# motorturn.net
KiCad netlist of a schematic drawn in Altium Designer
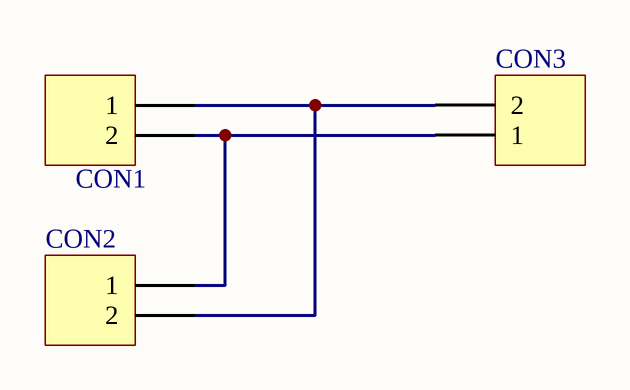
[diagram p0: motorturn.SchDoc]

(export (version "E")
  (design (tool "Eeschema 10.0.6"))
  (components
    (comp (ref "CON1")
      (value "MHDR1X2")
      (footprint "CON")
      (description "Header, 2-Pin")
      (fields (field (name "PUBLISHER") "Altium Limited"))
      (libsource (lib "Miscellaneous Connectors") (part "MHDR1X2"))
    )
    (comp (ref "CON2")
      (value "MHDR1X2")
      (footprint "CON")
      (description "Header, 2-Pin")
      (fields (field (name "PUBLISHER") "Altium Limited"))
      (libsource (lib "Miscellaneous Connectors") (part "MHDR1X2"))
    )
    (comp (ref "CON3")
      (value "MHDR1X2")
      (footprint "CON")
      (description "Header, 2-Pin")
      (fields (field (name "PUBLISHER") "Altium Limited"))
      (libsource (lib "") (part "MHDR1X2_1"))
    )
  )
  (nets
    (net (code "1") (name "Net-(CON1-Pad1)") (class "Default")
      (node (ref "CON1") (pin "1") (pinfunction "1_1") (pintype "passive"))
      (node (ref "CON2") (pin "2") (pinfunction "2_2") (pintype "passive"))
      (node (ref "CON3") (pin "2") (pinfunction "2_2") (pintype "passive"))
    )
    (net (code "2") (name "Net-(CON1-Pad2)") (class "Default")
      (node (ref "CON1") (pin "2") (pinfunction "2_2") (pintype "passive"))
      (node (ref "CON2") (pin "1") (pinfunction "1_1") (pintype "passive"))
      (node (ref "CON3") (pin "1") (pinfunction "1_1") (pintype "passive"))
    )
  )
)
